# Bluetooth.net
KiCad netlist of a schematic drawn in Altium Designer
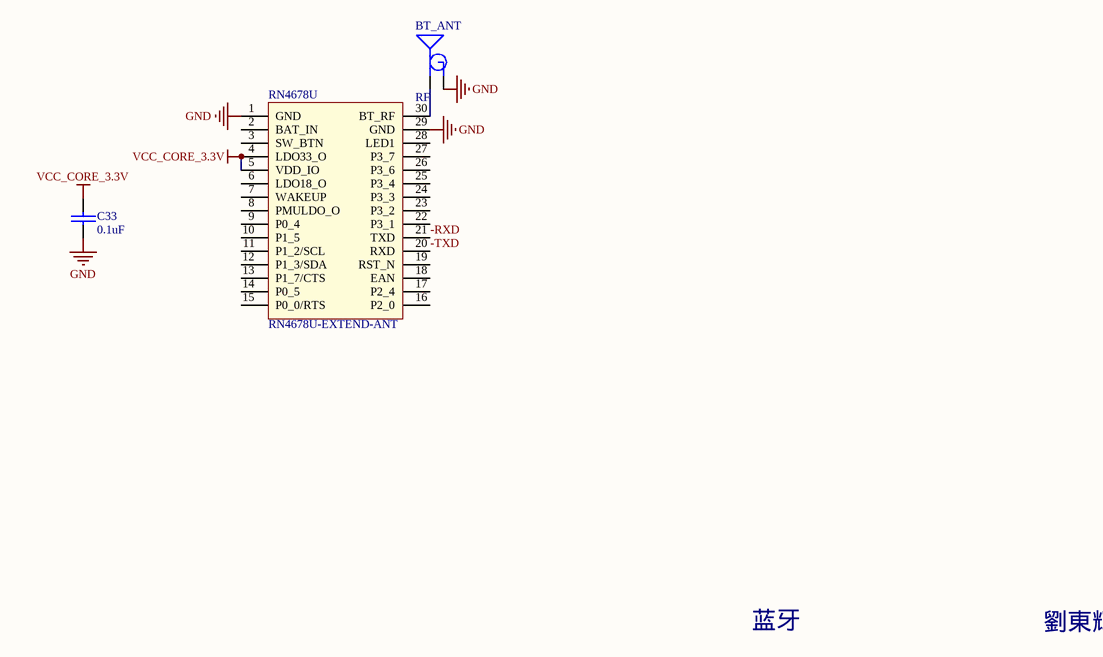
[diagram p0: Bluetooth.SchDoc]

(export (version "E")
  (design (tool "Eeschema 10.0.6"))
  (components
    (comp (ref "BT_ANT")
      (value "RF")
      (footprint "HIROSE_U.FL-R-SMT-1(10)")
      (libsource (lib "ANT") (part "RF"))
    )
    (comp (ref "C33")
      (value "0.1uF")
      (footprint "0805/2012 C3")
      (libsource (lib "*") (part "Pro39.tmp_22P_32"))
    )
    (comp (ref "RN4678U")
      (value "RN4678U-EXTEND-ANT")
      (footprint "RN4678U-EXTEND-ANT")
      (libsource (lib "Bluetooth") (part "RN4678U-EXTEND-ANT"))
    )
  )
  (nets
    (net (code "1") (name "/-RXD") (class "Default")
      (node (ref "RN4678U") (pin "21") (pinfunction "TXD_21") (pintype "passive"))
    )
    (net (code "2") (name "/-TXD") (class "Default")
      (node (ref "RN4678U") (pin "20") (pinfunction "RXD_20") (pintype "passive"))
    )
    (net (code "3") (name "GND") (class "Default")
      (node (ref "BT_ANT") (pin "2") (pintype "passive"))
      (node (ref "C33") (pin "2") (pintype "passive"))
      (node (ref "RN4678U") (pin "1") (pinfunction "GND_1") (pintype "passive"))
      (node (ref "RN4678U") (pin "29") (pinfunction "GND_29") (pintype "passive"))
    )
    (net (code "4") (name "Net-(RN4678U-BT_RF)") (class "Default")
      (node (ref "BT_ANT") (pin "1") (pintype "passive"))
      (node (ref "RN4678U") (pin "30") (pinfunction "BT_RF_30") (pintype "passive"))
    )
    (net (code "5") (name "VCC_CORE_3.3V") (class "Default")
      (node (ref "C33") (pin "1") (pintype "passive"))
      (node (ref "RN4678U") (pin "4") (pinfunction "LDO33_O_4") (pintype "passive"))
      (node (ref "RN4678U") (pin "5") (pinfunction "VDD_IO_5") (pintype "passive"))
    )
    (net (code "6") (name "unconnected-(RN4678U-BAT_IN-Pad2)") (class "Default")
      (node (ref "RN4678U") (pin "2") (pinfunction "BAT_IN_2") (pintype "passive"))
    )
    (net (code "7") (name "unconnected-(RN4678U-EAN-Pad18)") (class "Default")
      (node (ref "RN4678U") (pin "18") (pinfunction "EAN_18") (pintype "passive"))
    )
    (net (code "8") (name "unconnected-(RN4678U-LDO18_O-Pad6)") (class "Default")
      (node (ref "RN4678U") (pin "6") (pinfunction "LDO18_O_6") (pintype "passive"))
    )
    (net (code "9") (name "unconnected-(RN4678U-LED1-Pad28)") (class "Default")
      (node (ref "RN4678U") (pin "28") (pinfunction "LED1_28") (pintype "passive"))
    )
    (net (code "10") (name "unconnected-(RN4678U-P0_0{slash}RTS-Pad15)") (class "Default")
      (node (ref "RN4678U") (pin "15") (pinfunction "P0_0/RTS_15") (pintype "passive"))
    )
    (net (code "11") (name "unconnected-(RN4678U-P0_4-Pad9)") (class "Default")
      (node (ref "RN4678U") (pin "9") (pinfunction "P0_4_9") (pintype "passive"))
    )
    (net (code "12") (name "unconnected-(RN4678U-P0_5-Pad14)") (class "Default")
      (node (ref "RN4678U") (pin "14") (pinfunction "P0_5_14") (pintype "passive"))
    )
    (net (code "13") (name "unconnected-(RN4678U-P1_2{slash}SCL-Pad11)") (class "Default")
      (node (ref "RN4678U") (pin "11") (pinfunction "P1_2/SCL_11") (pintype "passive"))
    )
    (net (code "14") (name "unconnected-(RN4678U-P1_3{slash}SDA-Pad12)") (class "Default")
      (node (ref "RN4678U") (pin "12") (pinfunction "P1_3/SDA_12") (pintype "passive"))
    )
    (net (code "15") (name "unconnected-(RN4678U-P1_5-Pad10)") (class "Default")
      (node (ref "RN4678U") (pin "10") (pinfunction "P1_5_10") (pintype "passive"))
    )
    (net (code "16") (name "unconnected-(RN4678U-P1_7{slash}CTS-Pad13)") (class "Default")
      (node (ref "RN4678U") (pin "13") (pinfunction "P1_7/CTS_13") (pintype "passive"))
    )
    (net (code "17") (name "unconnected-(RN4678U-P2_0-Pad16)") (class "Default")
      (node (ref "RN4678U") (pin "16") (pinfunction "P2_0_16") (pintype "passive"))
    )
    (net (code "18") (name "unconnected-(RN4678U-P2_4-Pad17)") (class "Default")
      (node (ref "RN4678U") (pin "17") (pinfunction "P2_4_17") (pintype "passive"))
    )
    (net (code "19") (name "unconnected-(RN4678U-P3_1-Pad22)") (class "Default")
      (node (ref "RN4678U") (pin "22") (pinfunction "P3_1_22") (pintype "passive"))
    )
    (net (code "20") (name "unconnected-(RN4678U-P3_2-Pad23)") (class "Default")
      (node (ref "RN4678U") (pin "23") (pinfunction "P3_2_23") (pintype "passive"))
    )
    (net (code "21") (name "unconnected-(RN4678U-P3_3-Pad24)") (class "Default")
      (node (ref "RN4678U") (pin "24") (pinfunction "P3_3_24") (pintype "passive"))
    )
    (net (code "22") (name "unconnected-(RN4678U-P3_4-Pad25)") (class "Default")
      (node (ref "RN4678U") (pin "25") (pinfunction "P3_4_25") (pintype "passive"))
    )
    (net (code "23") (name "unconnected-(RN4678U-P3_6-Pad26)") (class "Default")
      (node (ref "RN4678U") (pin "26") (pinfunction "P3_6_26") (pintype "passive"))
    )
    (net (code "24") (name "unconnected-(RN4678U-P3_7-Pad27)") (class "Default")
      (node (ref "RN4678U") (pin "27") (pinfunction "P3_7_27") (pintype "passive"))
    )
    (net (code "25") (name "unconnected-(RN4678U-PMULDO_O-Pad8)") (class "Default")
      (node (ref "RN4678U") (pin "8") (pinfunction "PMULDO_O_8") (pintype "passive"))
    )
    (net (code "26") (name "unconnected-(RN4678U-RST_N-Pad19)") (class "Default")
      (node (ref "RN4678U") (pin "19") (pinfunction "RST_N_19") (pintype "passive"))
    )
    (net (code "27") (name "unconnected-(RN4678U-SW_BTN-Pad3)") (class "Default")
      (node (ref "RN4678U") (pin "3") (pinfunction "SW_BTN_3") (pintype "passive"))
    )
    (net (code "28") (name "unconnected-(RN4678U-WAKEUP-Pad7)") (class "Default")
      (node (ref "RN4678U") (pin "7") (pinfunction "WAKEUP_7") (pintype "passive"))
    )
  )
)
